# LED_Matrix.net
KiCad netlist of a schematic drawn in EAGLE
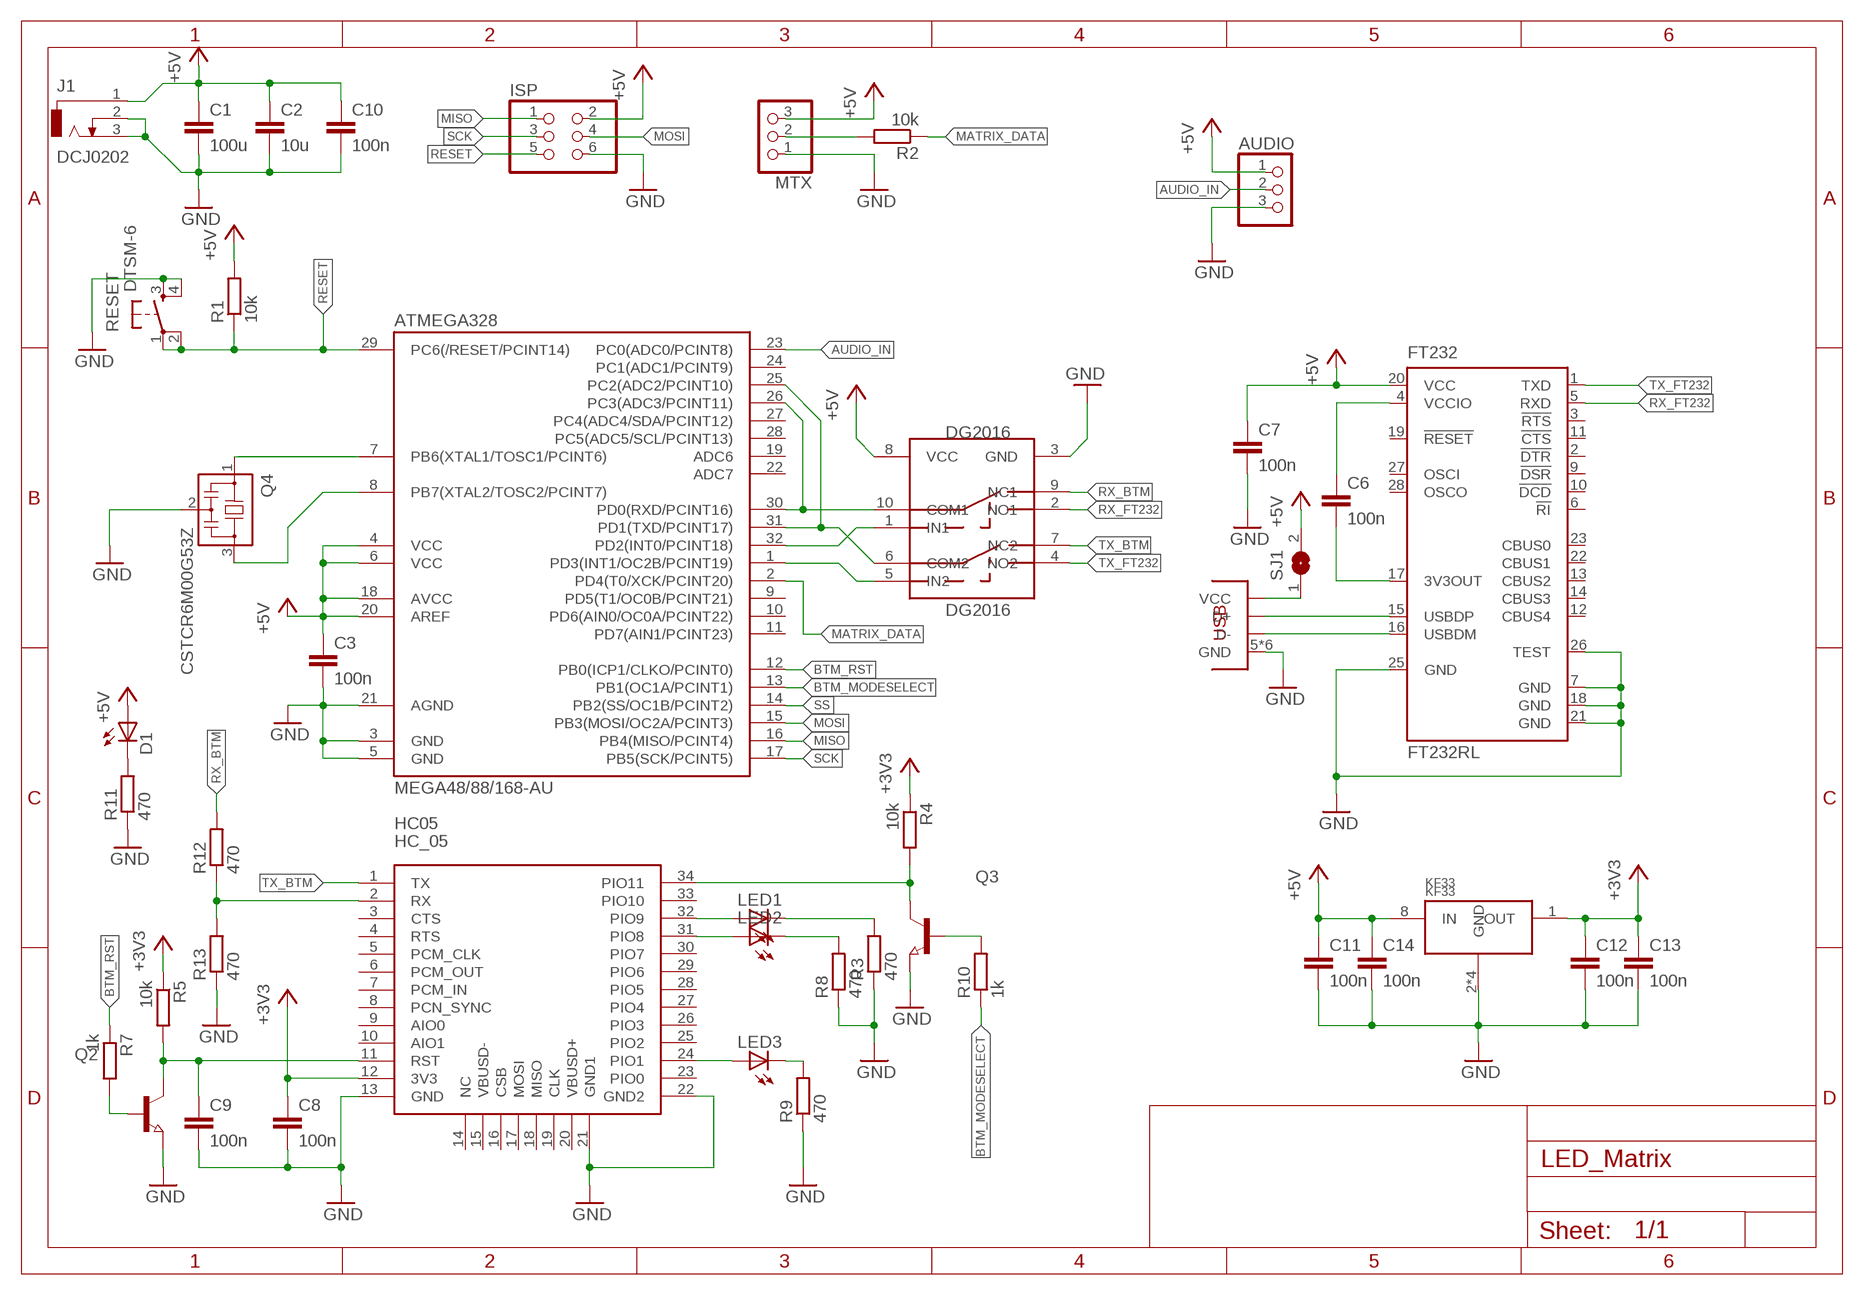
[diagram p0: schematic, sheet 1]

(export (version "E")
  (design (tool "Eeschema 10.0.6"))
  (components
    (comp (ref "ATMEGA328")
      (value "MEGA48/88/168-AU")
      (footprint "eagle-import:TQFP32-08")
      (libsource (lib "eagle-import") (part "MEGA48/88/168-AU"))
    )
    (comp (ref "AUDIO")
      (value "PINHD-1X3")
      (footprint "eagle-import:1X03")
      (libsource (lib "eagle-import") (part "PINHD-1X3"))
    )
    (comp (ref "C1")
      (value "100u")
      (footprint "eagle-import:C0805")
      (libsource (lib "eagle-import") (part "C-EUC0805"))
    )
    (comp (ref "C2")
      (value "10u")
      (footprint "eagle-import:C0805")
      (libsource (lib "eagle-import") (part "C-EUC0805"))
    )
    (comp (ref "C3")
      (value "100n")
      (footprint "eagle-import:C0805")
      (libsource (lib "eagle-import") (part "C-EUC0805"))
    )
    (comp (ref "C6")
      (value "100n")
      (footprint "eagle-import:C0805")
      (libsource (lib "eagle-import") (part "C-EUC0805"))
    )
    (comp (ref "C7")
      (value "100n")
      (footprint "eagle-import:C0805")
      (libsource (lib "eagle-import") (part "C-EUC0805"))
    )
    (comp (ref "C8")
      (value "100n")
      (footprint "eagle-import:C0805")
      (libsource (lib "eagle-import") (part "C-EUC0805"))
    )
    (comp (ref "C9")
      (value "100n")
      (footprint "eagle-import:C0805")
      (libsource (lib "eagle-import") (part "C-EUC0805"))
    )
    (comp (ref "C10")
      (value "100n")
      (footprint "eagle-import:C0805")
      (libsource (lib "eagle-import") (part "C-EUC0805"))
    )
    (comp (ref "C11")
      (value "100n")
      (footprint "eagle-import:C0805")
      (libsource (lib "eagle-import") (part "C-EUC0805"))
    )
    (comp (ref "C12")
      (value "100n")
      (footprint "eagle-import:C0805")
      (libsource (lib "eagle-import") (part "C-EUC0805"))
    )
    (comp (ref "C13")
      (value "100n")
      (footprint "eagle-import:C0805")
      (libsource (lib "eagle-import") (part "C-EUC0805"))
    )
    (comp (ref "C14")
      (value "100n")
      (footprint "eagle-import:C0805")
      (libsource (lib "eagle-import") (part "C-EUC0805"))
    )
    (comp (ref "D1")
      (value "LEDSML0805")
      (footprint "eagle-import:SML0805")
      (libsource (lib "eagle-import") (part "LEDSML0805"))
    )
    (comp (ref "DG2016")
      (value "DG2016")
      (footprint "eagle-import:MSOP10")
      (libsource (lib "eagle-import") (part "DG2016"))
    )
    (comp (ref "FT232")
      (value "FT232RL")
      (footprint "eagle-import:SSOP28")
      (libsource (lib "eagle-import") (part "FT232RL"))
    )
    (comp (ref "HC05")
      (value "HC_05")
      (footprint "eagle-import:BLUETOOTH_SMD")
      (libsource (lib "eagle-import") (part "HC_05"))
    )
    (comp (ref "ISP")
      (value "PINHD-2X3")
      (footprint "eagle-import:2X03")
      (libsource (lib "eagle-import") (part "PINHD-2X3"))
    )
    (comp (ref "J1")
      (value "DCJ0202")
      (footprint "eagle-import:DCJ0202")
      (libsource (lib "eagle-import") (part "DCJ0202"))
    )
    (comp (ref "KF33")
      (value "KF33")
      (footprint "eagle-import:SO08")
      (libsource (lib "eagle-import") (part "KF33"))
    )
    (comp (ref "LED1")
      (value "LEDSML0805")
      (footprint "eagle-import:SML0805")
      (libsource (lib "eagle-import") (part "LEDSML0805"))
    )
    (comp (ref "LED2")
      (value "LEDSML0805")
      (footprint "eagle-import:SML0805")
      (libsource (lib "eagle-import") (part "LEDSML0805"))
    )
    (comp (ref "LED3")
      (value "LEDSML0805")
      (footprint "eagle-import:SML0805")
      (libsource (lib "eagle-import") (part "LEDSML0805"))
    )
    (comp (ref "MTX")
      (value "PINHD-1X3")
      (footprint "eagle-import:1X03")
      (libsource (lib "eagle-import") (part "PINHD-1X3"))
    )
    (comp (ref "Q2")
      (value "NPN-TRANSISTOR_SOT23")
      (footprint "eagle-import:SOT23")
      (libsource (lib "eagle-import") (part "NPN-TRANSISTOR_SOT23"))
    )
    (comp (ref "Q3")
      (value "NPN-TRANSISTOR_SOT23")
      (footprint "eagle-import:SOT23")
      (libsource (lib "eagle-import") (part "NPN-TRANSISTOR_SOT23"))
    )
    (comp (ref "Q4")
      (value "CSTCR6M00G53Z")
      (footprint "eagle-import:CSTCR6M")
      (fields (field (name "MPN") "CSTCR6M00G53-R0"))
      (libsource (lib "eagle-import") (part "CSTCR6M00G53Z"))
    )
    (comp (ref "R1")
      (value "10k")
      (footprint "eagle-import:R0805")
      (libsource (lib "eagle-import") (part "R-EU_R0805"))
    )
    (comp (ref "R2")
      (value "10k")
      (footprint "eagle-import:R0805")
      (libsource (lib "eagle-import") (part "R-EU_R0805"))
    )
    (comp (ref "R3")
      (value "470")
      (footprint "eagle-import:R0805")
      (libsource (lib "eagle-import") (part "R-EU_R0805"))
    )
    (comp (ref "R4")
      (value "10k")
      (footprint "eagle-import:R0805")
      (libsource (lib "eagle-import") (part "R-EU_R0805"))
    )
    (comp (ref "R5")
      (value "10k")
      (footprint "eagle-import:R0805")
      (libsource (lib "eagle-import") (part "R-EU_R0805"))
    )
    (comp (ref "R7")
      (value "1k")
      (footprint "eagle-import:R0805")
      (libsource (lib "eagle-import") (part "R-EU_R0805"))
    )
    (comp (ref "R8")
      (value "470")
      (footprint "eagle-import:R0805")
      (libsource (lib "eagle-import") (part "R-EU_R0805"))
    )
    (comp (ref "R9")
      (value "470")
      (footprint "eagle-import:R0805")
      (libsource (lib "eagle-import") (part "R-EU_R0805"))
    )
    (comp (ref "R10")
      (value "1k")
      (footprint "eagle-import:R0805")
      (libsource (lib "eagle-import") (part "R-EU_R0805"))
    )
    (comp (ref "R11")
      (value "470")
      (footprint "eagle-import:R0805")
      (libsource (lib "eagle-import") (part "R-EU_R0805"))
    )
    (comp (ref "R12")
      (value "470")
      (footprint "eagle-import:R0805")
      (libsource (lib "eagle-import") (part "R-EU_R0805"))
    )
    (comp (ref "R13")
      (value "470")
      (footprint "eagle-import:R0805")
      (libsource (lib "eagle-import") (part "R-EU_R0805"))
    )
    (comp (ref "RESET")
      (value "DTSM-6")
      (footprint "eagle-import:DTSM-6")
      (libsource (lib "eagle-import") (part "DTSM-6"))
    )
    (comp (ref "SJ1") (value "SJ") (footprint "eagle-import:SJ") (libsource (lib "eagle-import") (part "SJ")))
    (comp (ref "USB")
      (value "MINI_USB")
      (footprint "eagle-import:USB_MINI")
      (libsource (lib "eagle-import") (part "MINI_USB"))
    )
  )
  (nets
    (net (code "1") (name "+3V3") (class "Default")
      (node (ref "C12") (pin "1") (pinfunction "1_1") (pintype "passive"))
      (node (ref "C13") (pin "1") (pinfunction "1_1") (pintype "passive"))
      (node (ref "C8") (pin "1") (pinfunction "1_1") (pintype "passive"))
      (node (ref "HC05") (pin "12") (pinfunction "3V3_12") (pintype "bidirectional"))
      (node (ref "KF33") (pin "1") (pinfunction "OUT_1") (pintype "power_in"))
      (node (ref "R4") (pin "1") (pinfunction "1_1") (pintype "passive"))
      (node (ref "R5") (pin "1") (pinfunction "1_1") (pintype "passive"))
    )
    (net (code "2") (name "+5V") (class "Default")
      (node (ref "ATMEGA328") (pin "18") (pinfunction "AVCC_18") (pintype "passive"))
      (node (ref "ATMEGA328") (pin "20") (pinfunction "AREF_20") (pintype "passive"))
      (node (ref "ATMEGA328") (pin "4") (pinfunction "VCC_4") (pintype "power_in"))
      (node (ref "ATMEGA328") (pin "6") (pinfunction "VCC_6") (pintype "power_in"))
      (node (ref "AUDIO") (pin "1") (pinfunction "1_1") (pintype "passive"))
      (node (ref "C1") (pin "1") (pinfunction "1_1") (pintype "passive"))
      (node (ref "C10") (pin "1") (pinfunction "1_1") (pintype "passive"))
      (node (ref "C11") (pin "1") (pinfunction "1_1") (pintype "passive"))
      (node (ref "C14") (pin "1") (pinfunction "1_1") (pintype "passive"))
      (node (ref "C2") (pin "1") (pinfunction "1_1") (pintype "passive"))
      (node (ref "C3") (pin "1") (pinfunction "1_1") (pintype "passive"))
      (node (ref "C7") (pin "1") (pinfunction "1_1") (pintype "passive"))
      (node (ref "D1") (pin "A") (pinfunction "A_A") (pintype "passive"))
      (node (ref "DG2016") (pin "8") (pinfunction "VCC_8") (pintype "bidirectional"))
      (node (ref "FT232") (pin "20") (pinfunction "VCC_20") (pintype "power_in"))
      (node (ref "ISP") (pin "2") (pinfunction "2_2") (pintype "passive"))
      (node (ref "J1") (pin "1") (pinfunction "1_1") (pintype "passive"))
      (node (ref "KF33") (pin "8") (pinfunction "IN_8") (pintype "power_in"))
      (node (ref "MTX") (pin "3") (pinfunction "3_3") (pintype "passive"))
      (node (ref "R1") (pin "2") (pinfunction "2_2") (pintype "passive"))
      (node (ref "SJ1") (pin "2") (pinfunction "2_2") (pintype "passive"))
    )
    (net (code "3") (name "AUDIO_IN") (class "Default")
      (node (ref "ATMEGA328") (pin "23") (pinfunction "PC0(ADC0/PCINT8)_23") (pintype "bidirectional"))
      (node (ref "AUDIO") (pin "2") (pinfunction "2_2") (pintype "passive"))
    )
    (net (code "4") (name "BTM_MODESELECT") (class "Default")
      (node (ref "ATMEGA328") (pin "13") (pinfunction "PB1(OC1A/PCINT1)_13") (pintype "bidirectional"))
      (node (ref "HC05") (pin "34") (pinfunction "PIO11_34") (pintype "bidirectional"))
      (node (ref "Q3") (pin "3") (pinfunction "C_3") (pintype "passive"))
      (node (ref "R10") (pin "1") (pinfunction "1_1") (pintype "passive"))
      (node (ref "R4") (pin "2") (pinfunction "2_2") (pintype "passive"))
    )
    (net (code "5") (name "BTM_RST") (class "Default")
      (node (ref "ATMEGA328") (pin "12") (pinfunction "PB0(ICP1/CLKO/PCINT0)_12") (pintype "bidirectional"))
      (node (ref "R7") (pin "1") (pinfunction "1_1") (pintype "passive"))
    )
    (net (code "6") (name "GND") (class "Default")
      (node (ref "ATMEGA328") (pin "21") (pinfunction "AGND_21") (pintype "power_in"))
      (node (ref "ATMEGA328") (pin "3") (pinfunction "GND_3") (pintype "power_in"))
      (node (ref "ATMEGA328") (pin "5") (pinfunction "GND_5") (pintype "power_in"))
      (node (ref "AUDIO") (pin "3") (pinfunction "3_3") (pintype "passive"))
      (node (ref "C1") (pin "2") (pinfunction "2_2") (pintype "passive"))
      (node (ref "C10") (pin "2") (pinfunction "2_2") (pintype "passive"))
      (node (ref "C11") (pin "2") (pinfunction "2_2") (pintype "passive"))
      (node (ref "C12") (pin "2") (pinfunction "2_2") (pintype "passive"))
      (node (ref "C13") (pin "2") (pinfunction "2_2") (pintype "passive"))
      (node (ref "C14") (pin "2") (pinfunction "2_2") (pintype "passive"))
      (node (ref "C2") (pin "2") (pinfunction "2_2") (pintype "passive"))
      (node (ref "C3") (pin "2") (pinfunction "2_2") (pintype "passive"))
      (node (ref "C7") (pin "2") (pinfunction "2_2") (pintype "passive"))
      (node (ref "C8") (pin "2") (pinfunction "2_2") (pintype "passive"))
      (node (ref "C9") (pin "2") (pinfunction "2_2") (pintype "passive"))
      (node (ref "DG2016") (pin "3") (pinfunction "GND_3") (pintype "bidirectional"))
      (node (ref "FT232") (pin "18") (pinfunction "GND_18") (pintype "power_in"))
      (node (ref "FT232") (pin "21") (pinfunction "GND_21") (pintype "power_in"))
      (node (ref "FT232") (pin "25") (pinfunction "GND_25") (pintype "power_in"))
      (node (ref "FT232") (pin "26") (pinfunction "TEST_26") (pintype "input"))
      (node (ref "FT232") (pin "7") (pinfunction "GND_7") (pintype "power_in"))
      (node (ref "HC05") (pin "13") (pinfunction "GND_13") (pintype "bidirectional"))
      (node (ref "HC05") (pin "21") (pinfunction "GND1_21") (pintype "bidirectional"))
      (node (ref "HC05") (pin "22") (pinfunction "GND2_22") (pintype "bidirectional"))
      (node (ref "ISP") (pin "6") (pinfunction "6_6") (pintype "passive"))
      (node (ref "J1") (pin "2") (pinfunction "2_2") (pintype "passive"))
      (node (ref "J1") (pin "3") (pinfunction "3_3") (pintype "passive"))
      (node (ref "KF33") (pin "2") (pinfunction "GND_2") (pintype "power_in"))
      (node (ref "KF33") (pin "3") (pinfunction "GND_3") (pintype "power_in"))
      (node (ref "KF33") (pin "6") (pinfunction "GND_6") (pintype "power_in"))
      (node (ref "KF33") (pin "7") (pinfunction "GND_7") (pintype "power_in"))
      (node (ref "MTX") (pin "1") (pinfunction "1_1") (pintype "passive"))
      (node (ref "Q2") (pin "2") (pinfunction "E_2") (pintype "passive"))
      (node (ref "Q3") (pin "2") (pinfunction "E_2") (pintype "passive"))
      (node (ref "Q4") (pin "2") (pinfunction "2_2") (pintype "passive"))
      (node (ref "R11") (pin "1") (pinfunction "1_1") (pintype "passive"))
      (node (ref "R13") (pin "1") (pinfunction "1_1") (pintype "passive"))
      (node (ref "R3") (pin "1") (pinfunction "1_1") (pintype "passive"))
      (node (ref "R8") (pin "1") (pinfunction "1_1") (pintype "passive"))
      (node (ref "R9") (pin "1") (pinfunction "1_1") (pintype "passive"))
      (node (ref "RESET") (pin "3") (pinfunction "3_3") (pintype "passive"))
      (node (ref "RESET") (pin "4") (pinfunction "4_4") (pintype "passive"))
      (node (ref "USB") (pin "5") (pinfunction "GND_5") (pintype "bidirectional"))
      (node (ref "USB") (pin "GND") (pinfunction "GND_GND") (pintype "bidirectional"))
      (node (ref "USB") (pin "GND1") (pinfunction "GND_GND1") (pintype "bidirectional"))
      (node (ref "USB") (pin "GND3") (pinfunction "GND_GND3") (pintype "bidirectional"))
      (node (ref "USB") (pin "GND4") (pinfunction "GND_GND4") (pintype "bidirectional"))
      (node (ref "USB") (pin "GND5") (pinfunction "GND_GND5") (pintype "bidirectional"))
    )
    (net (code "7") (name "MATRIX_DATA") (class "Default")
      (node (ref "ATMEGA328") (pin "2") (pinfunction "PD4(T0/XCK/PCINT20)_2") (pintype "bidirectional"))
      (node (ref "R2") (pin "1") (pinfunction "1_1") (pintype "passive"))
    )
    (net (code "8") (name "MISO") (class "Default")
      (node (ref "ATMEGA328") (pin "16") (pinfunction "PB4(MISO/PCINT4)_16") (pintype "bidirectional"))
      (node (ref "ISP") (pin "1") (pinfunction "1_1") (pintype "passive"))
    )
    (net (code "9") (name "MOSI") (class "Default")
      (node (ref "ATMEGA328") (pin "15") (pinfunction "PB3(MOSI/OC2A/PCINT3)_15") (pintype "bidirectional"))
      (node (ref "ISP") (pin "4") (pinfunction "4_4") (pintype "passive"))
    )
    (net (code "10") (name "Net-(ATMEGA328-PB6(XTAL1{slash}TOSC1{slash}PCINT6))") (class "Default")
      (node (ref "ATMEGA328") (pin "7") (pinfunction "PB6(XTAL1/TOSC1/PCINT6)_7") (pintype "bidirectional"))
      (node (ref "Q4") (pin "1") (pinfunction "1_1") (pintype "passive"))
    )
    (net (code "11") (name "Net-(ATMEGA328-PB7(XTAL2{slash}TOSC2{slash}PCINT7))") (class "Default")
      (node (ref "ATMEGA328") (pin "8") (pinfunction "PB7(XTAL2/TOSC2/PCINT7)_8") (pintype "bidirectional"))
      (node (ref "Q4") (pin "3") (pinfunction "3_3") (pintype "passive"))
    )
    (net (code "12") (name "Net-(ATMEGA328-PC2(ADC2{slash}PCINT10))") (class "Default")
      (node (ref "ATMEGA328") (pin "25") (pinfunction "PC2(ADC2/PCINT10)_25") (pintype "bidirectional"))
      (node (ref "ATMEGA328") (pin "31") (pinfunction "PD1(TXD/PCINT17)_31") (pintype "bidirectional"))
      (node (ref "DG2016") (pin "6") (pinfunction "COM2_6") (pintype "bidirectional"))
    )
    (net (code "13") (name "Net-(ATMEGA328-PC3(ADC3{slash}PCINT11))") (class "Default")
      (node (ref "ATMEGA328") (pin "26") (pinfunction "PC3(ADC3/PCINT11)_26") (pintype "bidirectional"))
      (node (ref "ATMEGA328") (pin "30") (pinfunction "PD0(RXD/PCINT16)_30") (pintype "bidirectional"))
      (node (ref "DG2016") (pin "10") (pinfunction "COM1_10") (pintype "bidirectional"))
    )
    (net (code "14") (name "Net-(ATMEGA328-PD2(INT0{slash}PCINT18))") (class "Default")
      (node (ref "ATMEGA328") (pin "32") (pinfunction "PD2(INT0/PCINT18)_32") (pintype "bidirectional"))
      (node (ref "DG2016") (pin "1") (pinfunction "IN1_1") (pintype "bidirectional"))
    )
    (net (code "15") (name "Net-(ATMEGA328-PD3(INT1{slash}OC2B{slash}PCINT19))") (class "Default")
      (node (ref "ATMEGA328") (pin "1") (pinfunction "PD3(INT1/OC2B/PCINT19)_1") (pintype "bidirectional"))
      (node (ref "DG2016") (pin "5") (pinfunction "IN2_5") (pintype "bidirectional"))
    )
    (net (code "16") (name "Net-(D1-PadC)") (class "Default")
      (node (ref "D1") (pin "C") (pinfunction "C_C") (pintype "passive"))
      (node (ref "R11") (pin "2") (pinfunction "2_2") (pintype "passive"))
    )
    (net (code "17") (name "Net-(FT232-3V3OUT)") (class "Default")
      (node (ref "C6") (pin "2") (pinfunction "2_2") (pintype "passive"))
      (node (ref "FT232") (pin "17") (pinfunction "3V3OUT_17") (pintype "output"))
    )
    (net (code "18") (name "Net-(FT232-USBDM)") (class "Default")
      (node (ref "FT232") (pin "16") (pinfunction "USBDM_16") (pintype "bidirectional"))
      (node (ref "USB") (pin "2") (pinfunction "D-_2") (pintype "bidirectional"))
    )
    (net (code "19") (name "Net-(FT232-USBDP)") (class "Default")
      (node (ref "FT232") (pin "15") (pinfunction "USBDP_15") (pintype "bidirectional"))
      (node (ref "USB") (pin "3") (pinfunction "D+_3") (pintype "bidirectional"))
    )
    (net (code "20") (name "Net-(FT232-VCCIO)") (class "Default")
      (node (ref "C6") (pin "1") (pinfunction "1_1") (pintype "passive"))
      (node (ref "FT232") (pin "4") (pinfunction "VCCIO_4") (pintype "power_in"))
    )
    (net (code "21") (name "Net-(HC05-PIO1)") (class "Default")
      (node (ref "HC05") (pin "24") (pinfunction "PIO1_24") (pintype "bidirectional"))
      (node (ref "LED3") (pin "A") (pinfunction "A_A") (pintype "passive"))
    )
    (net (code "22") (name "Net-(HC05-PIO8)") (class "Default")
      (node (ref "HC05") (pin "31") (pinfunction "PIO8_31") (pintype "bidirectional"))
      (node (ref "LED2") (pin "A") (pinfunction "A_A") (pintype "passive"))
    )
    (net (code "23") (name "Net-(HC05-PIO9)") (class "Default")
      (node (ref "HC05") (pin "32") (pinfunction "PIO9_32") (pintype "bidirectional"))
      (node (ref "LED1") (pin "A") (pinfunction "A_A") (pintype "passive"))
    )
    (net (code "24") (name "Net-(HC05-RST)") (class "Default")
      (node (ref "C9") (pin "1") (pinfunction "1_1") (pintype "passive"))
      (node (ref "HC05") (pin "11") (pinfunction "RST_11") (pintype "bidirectional"))
      (node (ref "Q2") (pin "3") (pinfunction "C_3") (pintype "passive"))
      (node (ref "R5") (pin "2") (pinfunction "2_2") (pintype "passive"))
    )
    (net (code "25") (name "Net-(HC05-RX)") (class "Default")
      (node (ref "HC05") (pin "2") (pinfunction "RX_2") (pintype "bidirectional"))
      (node (ref "R12") (pin "1") (pinfunction "1_1") (pintype "passive"))
      (node (ref "R13") (pin "2") (pinfunction "2_2") (pintype "passive"))
    )
    (net (code "26") (name "Net-(LED1-PadC)") (class "Default")
      (node (ref "LED1") (pin "C") (pinfunction "C_C") (pintype "passive"))
      (node (ref "R3") (pin "2") (pinfunction "2_2") (pintype "passive"))
    )
    (net (code "27") (name "Net-(LED2-PadC)") (class "Default")
      (node (ref "LED2") (pin "C") (pinfunction "C_C") (pintype "passive"))
      (node (ref "R8") (pin "2") (pinfunction "2_2") (pintype "passive"))
    )
    (net (code "28") (name "Net-(LED3-PadC)") (class "Default")
      (node (ref "LED3") (pin "C") (pinfunction "C_C") (pintype "passive"))
      (node (ref "R9") (pin "2") (pinfunction "2_2") (pintype "passive"))
    )
    (net (code "29") (name "Net-(MTX-Pad2)") (class "Default")
      (node (ref "MTX") (pin "2") (pinfunction "2_2") (pintype "passive"))
      (node (ref "R2") (pin "2") (pinfunction "2_2") (pintype "passive"))
    )
    (net (code "30") (name "Net-(Q2-B)") (class "Default")
      (node (ref "Q2") (pin "1") (pinfunction "B_1") (pintype "passive"))
      (node (ref "R7") (pin "2") (pinfunction "2_2") (pintype "passive"))
    )
    (net (code "31") (name "Net-(Q3-B)") (class "Default")
      (node (ref "Q3") (pin "1") (pinfunction "B_1") (pintype "passive"))
      (node (ref "R10") (pin "2") (pinfunction "2_2") (pintype "passive"))
    )
    (net (code "32") (name "Net-(USB-VCC)") (class "Default")
      (node (ref "SJ1") (pin "1") (pinfunction "1_1") (pintype "passive"))
      (node (ref "USB") (pin "1") (pinfunction "VCC_1") (pintype "bidirectional"))
    )
    (net (code "33") (name "RESET") (class "Default")
      (node (ref "ATMEGA328") (pin "29") (pinfunction "PC6(/RESET/PCINT14)_29") (pintype "bidirectional"))
      (node (ref "ISP") (pin "5") (pinfunction "5_5") (pintype "passive"))
      (node (ref "R1") (pin "1") (pinfunction "1_1") (pintype "passive"))
      (node (ref "RESET") (pin "1") (pinfunction "1_1") (pintype "passive"))
      (node (ref "RESET") (pin "2") (pinfunction "2_2") (pintype "passive"))
    )
    (net (code "34") (name "RX_BTM") (class "Default")
      (node (ref "DG2016") (pin "9") (pinfunction "NC1_9") (pintype "bidirectional"))
      (node (ref "R12") (pin "2") (pinfunction "2_2") (pintype "passive"))
    )
    (net (code "35") (name "RX_FT232") (class "Default")
      (node (ref "DG2016") (pin "2") (pinfunction "NO1_2") (pintype "bidirectional"))
      (node (ref "FT232") (pin "5") (pinfunction "RXD_5") (pintype "input"))
    )
    (net (code "36") (name "SCK") (class "Default")
      (node (ref "ATMEGA328") (pin "17") (pinfunction "PB5(SCK/PCINT5)_17") (pintype "bidirectional"))
      (node (ref "ISP") (pin "3") (pinfunction "3_3") (pintype "passive"))
    )
    (net (code "37") (name "SS") (class "Default")
      (node (ref "ATMEGA328") (pin "14") (pinfunction "PB2(SS/OC1B/PCINT2)_14") (pintype "bidirectional"))
    )
    (net (code "38") (name "TX_BTM") (class "Default")
      (node (ref "DG2016") (pin "7") (pinfunction "NC2_7") (pintype "bidirectional"))
      (node (ref "HC05") (pin "1") (pinfunction "TX_1") (pintype "bidirectional"))
    )
    (net (code "39") (name "TX_FT232") (class "Default")
      (node (ref "DG2016") (pin "4") (pinfunction "NO2_4") (pintype "bidirectional"))
      (node (ref "FT232") (pin "1") (pinfunction "TXD_1") (pintype "output"))
    )
    (net (code "40") (name "unconnected-(ATMEGA328-ADC6-Pad19)") (class "Default")
      (node (ref "ATMEGA328") (pin "19") (pinfunction "ADC6_19") (pintype "passive"))
    )
    (net (code "41") (name "unconnected-(ATMEGA328-ADC7-Pad22)") (class "Default")
      (node (ref "ATMEGA328") (pin "22") (pinfunction "ADC7_22") (pintype "passive"))
    )
    (net (code "42") (name "unconnected-(ATMEGA328-PC1(ADC1{slash}PCINT9)-Pad24)") (class "Default")
      (node (ref "ATMEGA328") (pin "24") (pinfunction "PC1(ADC1/PCINT9)_24") (pintype "bidirectional"))
    )
    (net (code "43") (name "unconnected-(ATMEGA328-PC4(ADC4{slash}SDA{slash}PCINT12)-Pad27)") (class "Default")
      (node (ref "ATMEGA328") (pin "27") (pinfunction "PC4(ADC4/SDA/PCINT12)_27") (pintype "bidirectional"))
    )
    (net (code "44") (name "unconnected-(ATMEGA328-PC5(ADC5{slash}SCL{slash}PCINT13)-Pad28)") (class "Default")
      (node (ref "ATMEGA328") (pin "28") (pinfunction "PC5(ADC5/SCL/PCINT13)_28") (pintype "bidirectional"))
    )
    (net (code "45") (name "unconnected-(ATMEGA328-PD5(T1{slash}OC0B{slash}PCINT21)-Pad9)") (class "Default")
      (node (ref "ATMEGA328") (pin "9") (pinfunction "PD5(T1/OC0B/PCINT21)_9") (pintype "bidirectional"))
    )
    (net (code "46") (name "unconnected-(ATMEGA328-PD6(AIN0{slash}OC0A{slash}PCINT22)-Pad10)") (class "Default")
      (node (ref "ATMEGA328") (pin "10") (pinfunction "PD6(AIN0/OC0A/PCINT22)_10") (pintype "bidirectional"))
    )
    (net (code "47") (name "unconnected-(ATMEGA328-PD7(AIN1{slash}PCINT23)-Pad11)") (class "Default")
      (node (ref "ATMEGA328") (pin "11") (pinfunction "PD7(AIN1/PCINT23)_11") (pintype "bidirectional"))
    )
    (net (code "48") (name "unconnected-(FT232-CBUS0-Pad23)") (class "Default")
      (node (ref "FT232") (pin "23") (pinfunction "CBUS0_23") (pintype "bidirectional"))
    )
    (net (code "49") (name "unconnected-(FT232-CBUS1-Pad22)") (class "Default")
      (node (ref "FT232") (pin "22") (pinfunction "CBUS1_22") (pintype "bidirectional"))
    )
    (net (code "50") (name "unconnected-(FT232-CBUS2-Pad13)") (class "Default")
      (node (ref "FT232") (pin "13") (pinfunction "CBUS2_13") (pintype "bidirectional"))
    )
    (net (code "51") (name "unconnected-(FT232-CBUS3-Pad14)") (class "Default")
      (node (ref "FT232") (pin "14") (pinfunction "CBUS3_14") (pintype "bidirectional"))
    )
    (net (code "52") (name "unconnected-(FT232-CBUS4-Pad12)") (class "Default")
      (node (ref "FT232") (pin "12") (pinfunction "CBUS4_12") (pintype "bidirectional"))
    )
    (net (code "53") (name "unconnected-(FT232-OSCI-Pad27)") (class "Default")
      (node (ref "FT232") (pin "27") (pinfunction "OSCI_27") (pintype "input"))
    )
    (net (code "54") (name "unconnected-(FT232-OSCO-Pad28)") (class "Default")
      (node (ref "FT232") (pin "28") (pinfunction "OSCO_28") (pintype "output"))
    )
    (net (code "55") (name "unconnected-(FT232-~{CTS}-Pad11)") (class "Default")
      (node (ref "FT232") (pin "11") (pinfunction "~{CTS}_11") (pintype "input"))
    )
    (net (code "56") (name "unconnected-(FT232-~{DCD}-Pad10)") (class "Default")
      (node (ref "FT232") (pin "10") (pinfunction "~{DCD}_10") (pintype "input"))
    )
    (net (code "57") (name "unconnected-(FT232-~{DSR}-Pad9)") (class "Default")
      (node (ref "FT232") (pin "9") (pinfunction "~{DSR}_9") (pintype "input"))
    )
    (net (code "58") (name "unconnected-(FT232-~{DTR}-Pad2)") (class "Default")
      (node (ref "FT232") (pin "2") (pinfunction "~{DTR}_2") (pintype "output"))
    )
    (net (code "59") (name "unconnected-(FT232-~{RESET}-Pad19)") (class "Default")
      (node (ref "FT232") (pin "19") (pinfunction "~{RESET}_19") (pintype "input"))
    )
    (net (code "60") (name "unconnected-(FT232-~{RI}-Pad6)") (class "Default")
      (node (ref "FT232") (pin "6") (pinfunction "~{RI}_6") (pintype "input"))
    )
    (net (code "61") (name "unconnected-(FT232-~{RTS}-Pad3)") (class "Default")
      (node (ref "FT232") (pin "3") (pinfunction "~{RTS}_3") (pintype "output"))
    )
    (net (code "62") (name "unconnected-(HC05-AIO0-Pad9)") (class "Default")
      (node (ref "HC05") (pin "9") (pinfunction "AIO0_9") (pintype "bidirectional"))
    )
    (net (code "63") (name "unconnected-(HC05-AIO1-Pad10)") (class "Default")
      (node (ref "HC05") (pin "10") (pinfunction "AIO1_10") (pintype "bidirectional"))
    )
    (net (code "64") (name "unconnected-(HC05-CLK-Pad19)") (class "Default")
      (node (ref "HC05") (pin "19") (pinfunction "CLK_19") (pintype "bidirectional"))
    )
    (net (code "65") (name "unconnected-(HC05-CSB-Pad16)") (class "Default")
      (node (ref "HC05") (pin "16") (pinfunction "CSB_16") (pintype "bidirectional"))
    )
    (net (code "66") (name "unconnected-(HC05-CTS-Pad3)") (class "Default")
      (node (ref "HC05") (pin "3") (pinfunction "CTS_3") (pintype "bidirectional"))
    )
    (net (code "67") (name "unconnected-(HC05-MISO-Pad18)") (class "Default")
      (node (ref "HC05") (pin "18") (pinfunction "MISO_18") (pintype "bidirectional"))
    )
    (net (code "68") (name "unconnected-(HC05-MOSI-Pad17)") (class "Default")
      (node (ref "HC05") (pin "17") (pinfunction "MOSI_17") (pintype "bidirectional"))
    )
    (net (code "69") (name "unconnected-(HC05-NC-Pad14)") (class "Default")
      (node (ref "HC05") (pin "14") (pinfunction "NC_14") (pintype "bidirectional"))
    )
    (net (code "70") (name "unconnected-(HC05-PCM_CLK-Pad5)") (class "Default")
      (node (ref "HC05") (pin "5") (pinfunction "PCM_CLK_5") (pintype "bidirectional"))
    )
    (net (code "71") (name "unconnected-(HC05-PCM_IN-Pad7)") (class "Default")
      (node (ref "HC05") (pin "7") (pinfunction "PCM_IN_7") (pintype "bidirectional"))
    )
    (net (code "72") (name "unconnected-(HC05-PCM_OUT-Pad6)") (class "Default")
      (node (ref "HC05") (pin "6") (pinfunction "PCM_OUT_6") (pintype "bidirectional"))
    )
    (net (code "73") (name "unconnected-(HC05-PCN_SYNC-Pad8)") (class "Default")
      (node (ref "HC05") (pin "8") (pinfunction "PCN_SYNC_8") (pintype "bidirectional"))
    )
    (net (code "74") (name "unconnected-(HC05-PIO0-Pad23)") (class "Default")
      (node (ref "HC05") (pin "23") (pinfunction "PIO0_23") (pintype "bidirectional"))
    )
    (net (code "75") (name "unconnected-(HC05-PIO2-Pad25)") (class "Default")
      (node (ref "HC05") (pin "25") (pinfunction "PIO2_25") (pintype "bidirectional"))
    )
    (net (code "76") (name "unconnected-(HC05-PIO3-Pad26)") (class "Default")
      (node (ref "HC05") (pin "26") (pinfunction "PIO3_26") (pintype "bidirectional"))
    )
    (net (code "77") (name "unconnected-(HC05-PIO4-Pad27)") (class "Default")
      (node (ref "HC05") (pin "27") (pinfunction "PIO4_27") (pintype "bidirectional"))
    )
    (net (code "78") (name "unconnected-(HC05-PIO5-Pad28)") (class "Default")
      (node (ref "HC05") (pin "28") (pinfunction "PIO5_28") (pintype "bidirectional"))
    )
    (net (code "79") (name "unconnected-(HC05-PIO6-Pad29)") (class "Default")
      (node (ref "HC05") (pin "29") (pinfunction "PIO6_29") (pintype "bidirectional"))
    )
    (net (code "80") (name "unconnected-(HC05-PIO7-Pad30)") (class "Default")
      (node (ref "HC05") (pin "30") (pinfunction "PIO7_30") (pintype "bidirectional"))
    )
    (net (code "81") (name "unconnected-(HC05-PIO10-Pad33)") (class "Default")
      (node (ref "HC05") (pin "33") (pinfunction "PIO10_33") (pintype "bidirectional"))
    )
    (net (code "82") (name "unconnected-(HC05-RTS-Pad4)") (class "Default")
      (node (ref "HC05") (pin "4") (pinfunction "RTS_4") (pintype "bidirectional"))
    )
    (net (code "83") (name "unconnected-(HC05-VBUSD+-Pad20)") (class "Default")
      (node (ref "HC05") (pin "20") (pinfunction "VBUSD+_20") (pintype "bidirectional"))
    )
    (net (code "84") (name "unconnected-(HC05-VBUSD--Pad15)") (class "Default")
      (node (ref "HC05") (pin "15") (pinfunction "VBUSD-_15") (pintype "bidirectional"))
    )
  )
)
